# connectors-dribbler.net
KiCad netlist of a schematic drawn in Altium Designer
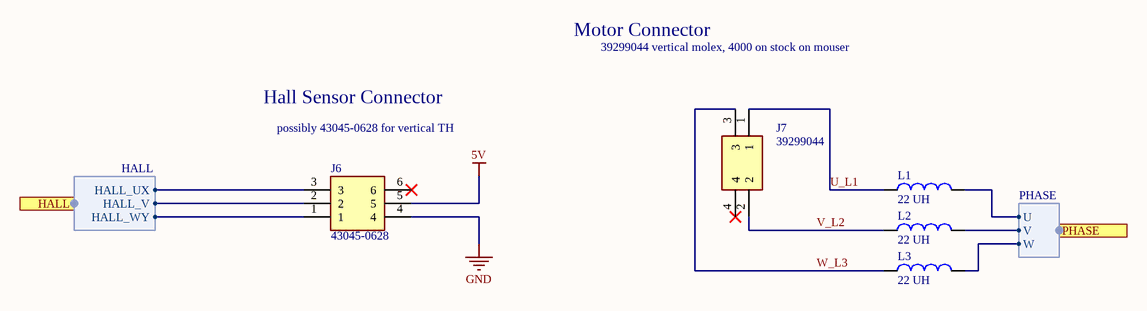
[diagram p0: connectors-dribbler.SchDoc]

(export (version "E")
  (design (tool "Eeschema 10.0.6"))
  (components
    (comp (ref "J6")
      (value "43045-0628")
      (footprint "430450628")
      (description "Molex 43045-0628 6POS Microfit\r\ndual row, Vertical")
      (fields (field (name "PART NUMBER") "CN HDR 6POS Molex 43045-0628"))
      (libsource (lib "Connector_Library") (part "CN HDR 6POS Molex 43045-0628"))
    )
    (comp (ref "J7")
      (value "39299044")
      (footprint "39299044")
      (description "Molex 39299044 4POS Minifit\r\ndual row, vertical")
      (fields (field (name "PART NUMBER") "CN HDR 4POS Molex 39299044 VERT"))
      (libsource (lib "Connector_Library") (part "CN HDR 4POS Molex 39299044 VERT"))
    )
    (comp (ref "L1")
      (value "22 UH")
      (footprint "EATON _HCM1A1307V2-220-R")
      (description "Automotive Grade High Current Power Inductor 22uH 6A 28.8mOhm 5MHz SRF 2-Pin Surface Mount T/R")
      (fields (field (name "PART NUMBER") "IND 22UH 6A 33.1 mOHM SMD"))
      (libsource (lib "Inductor_Library") (part "IND 22UH 6A 33.1 mOHM SMD"))
    )
    (comp (ref "L2")
      (value "22 UH")
      (footprint "EATON _HCM1A1307V2-220-R")
      (description "Automotive Grade High Current Power Inductor 22uH 6A 28.8mOhm 5MHz SRF 2-Pin Surface Mount T/R")
      (fields (field (name "PART NUMBER") "IND 22UH 6A 33.1 mOHM SMD"))
      (libsource (lib "Inductor_Library") (part "IND 22UH 6A 33.1 mOHM SMD"))
    )
    (comp (ref "L3")
      (value "22 UH")
      (footprint "EATON _HCM1A1307V2-220-R")
      (description "Automotive Grade High Current Power Inductor 22uH 6A 28.8mOhm 5MHz SRF 2-Pin Surface Mount T/R")
      (fields (field (name "PART NUMBER") "IND 22UH 6A 33.1 mOHM SMD"))
      (libsource (lib "Inductor_Library") (part "IND 22UH 6A 33.1 mOHM SMD"))
    )
  )
  (nets
    (net (code "3") (name "/HALL_UX") (class "Default")
      (node (ref "J6") (pin "3") (pinfunction "3_3") (pintype "passive"))
    )
    (net (code "4") (name "/HALL_V") (class "Default")
      (node (ref "J6") (pin "2") (pinfunction "2_2") (pintype "passive"))
    )
    (net (code "5") (name "/HALL_WY") (class "Default")
      (node (ref "J6") (pin "1") (pinfunction "1_1") (pintype "passive"))
    )
    (net (code "6") (name "/U") (class "Default")
      (node (ref "L1") (pin "2") (pinfunction "2_2") (pintype "passive"))
    )
    (net (code "7") (name "/U_L1") (class "Default")
      (node (ref "J7") (pin "1") (pinfunction "1_1") (pintype "passive"))
      (node (ref "L1") (pin "1") (pinfunction "1_1") (pintype "passive"))
    )
    (net (code "8") (name "/V") (class "Default")
      (node (ref "L2") (pin "2") (pinfunction "2_2") (pintype "passive"))
    )
    (net (code "9") (name "/V_L2") (class "Default")
      (node (ref "J7") (pin "2") (pinfunction "2_2") (pintype "passive"))
      (node (ref "L2") (pin "1") (pinfunction "1_1") (pintype "passive"))
    )
    (net (code "10") (name "/W") (class "Default")
      (node (ref "L3") (pin "2") (pinfunction "2_2") (pintype "passive"))
    )
    (net (code "11") (name "/W_L3") (class "Default")
      (node (ref "J7") (pin "3") (pinfunction "3_3") (pintype "passive"))
      (node (ref "L3") (pin "1") (pinfunction "1_1") (pintype "passive"))
    )
    (net (code "14") (name "5V") (class "Default")
      (node (ref "J6") (pin "5") (pinfunction "5_5") (pintype "passive"))
    )
    (net (code "15") (name "GND") (class "Default")
      (node (ref "J6") (pin "4") (pinfunction "4_4") (pintype "passive"))
    )
    (net (code "16") (name "unconnected-(J6-Pad6)") (class "Default")
      (node (ref "J6") (pin "6") (pinfunction "6_6") (pintype "passive+no_connect"))
    )
    (net (code "17") (name "unconnected-(J7-Pad4)") (class "Default")
      (node (ref "J7") (pin "4") (pinfunction "4_4") (pintype "passive+no_connect"))
    )
  )
)
